# G2G-I_Module.net
KiCad netlist of a schematic drawn in Altium Designer
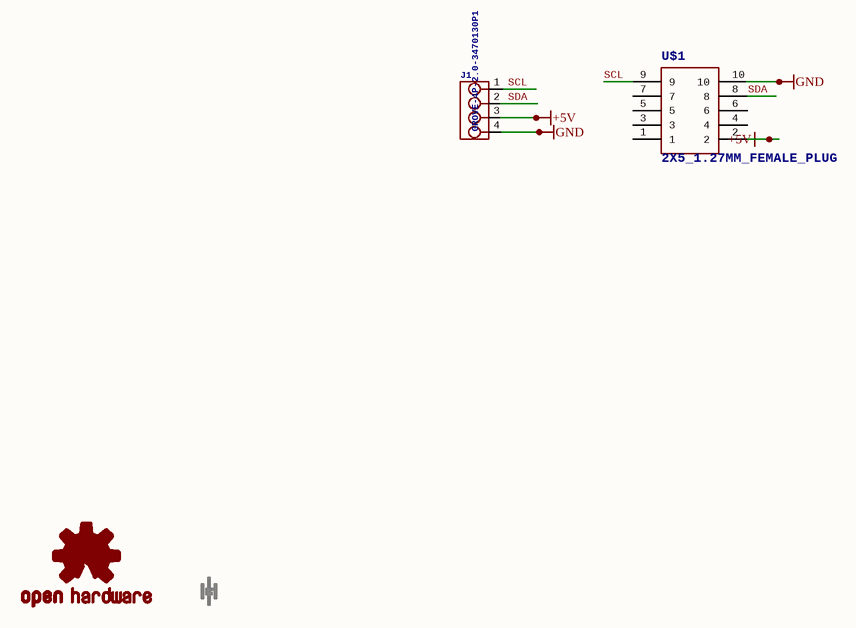
[diagram p0: G2G-I Module.SchDoc]

(export (version "E")
  (design (tool "Eeschema 10.0.6"))
  (components
    (comp (ref "J1")
      (value "GROVE-4P-2.0-3470130P1")
      (footprint "4P-2.0")
      (fields (field (name ">NAME") "J1") (field (name ">VALUE") "GROVE-4P-2.0-3470130P1"))
      (libsource (lib "SoftDust") (part "GROVE-4P-2.0-3470130P1"))
    )
    (comp (ref "LOGO1")
      (value "OSHW-LOGOS")
      (footprint "OSHW-LOGO-S")
      (libsource (lib "SparkFun-Aesthetics") (part "OSHW-LOGOS"))
    )
    (comp (ref "U$1")
      (value "2X5_1.27MM_FEMALE_PLUG")
      (footprint "2X5_1.27MM_FEMALE_PLUG")
      (fields (field (name ">NAME") "U$1") (field (name ">VALUE") "2X5_1.27MM_FEMALE_PLUG"))
      (libsource (lib "SoftDust") (part "2X5_1.27MM_FEMALE_PLUG"))
    )
    (comp (ref "U$2")
      (value "GADGETEER_LOGO_SMALL")
      (footprint "GADGETEER_LOGO_SMALL")
      (libsource (lib "SoftDust") (part "GADGETEER_LOGO_SMALL"))
    )
  )
  (nets
    (net (code "1") (name "+5V") (class "Default")
      (node (ref "J1") (pin "3") (pinfunction "3_3") (pintype "passive"))
      (node (ref "U$1") (pin "2") (pinfunction "2_2") (pintype "passive"))
    )
    (net (code "2") (name "/SCL") (class "Default")
      (node (ref "J1") (pin "1") (pinfunction "1_1") (pintype "passive"))
      (node (ref "U$1") (pin "9") (pinfunction "9_9") (pintype "passive"))
    )
    (net (code "3") (name "/SDA") (class "Default")
      (node (ref "J1") (pin "2") (pinfunction "2_2") (pintype "passive"))
      (node (ref "U$1") (pin "8") (pinfunction "8_8") (pintype "passive"))
    )
    (net (code "4") (name "GND") (class "Default")
      (node (ref "J1") (pin "4") (pinfunction "4_4") (pintype "passive"))
      (node (ref "U$1") (pin "10") (pinfunction "10_10") (pintype "passive"))
    )
    (net (code "5") (name "unconnected-(U$1-Pad1)") (class "Default")
      (node (ref "U$1") (pin "1") (pinfunction "1_1") (pintype "passive"))
    )
    (net (code "6") (name "unconnected-(U$1-Pad3)") (class "Default")
      (node (ref "U$1") (pin "3") (pinfunction "3_3") (pintype "passive"))
    )
    (net (code "7") (name "unconnected-(U$1-Pad4)") (class "Default")
      (node (ref "U$1") (pin "4") (pinfunction "4_4") (pintype "passive"))
    )
    (net (code "8") (name "unconnected-(U$1-Pad5)") (class "Default")
      (node (ref "U$1") (pin "5") (pinfunction "5_5") (pintype "passive"))
    )
    (net (code "9") (name "unconnected-(U$1-Pad6)") (class "Default")
      (node (ref "U$1") (pin "6") (pinfunction "6_6") (pintype "passive"))
    )
    (net (code "10") (name "unconnected-(U$1-Pad7)") (class "Default")
      (node (ref "U$1") (pin "7") (pinfunction "7_7") (pintype "passive"))
    )
  )
)
